# PowerSupply.net
KiCad netlist of a schematic drawn in Altium Designer
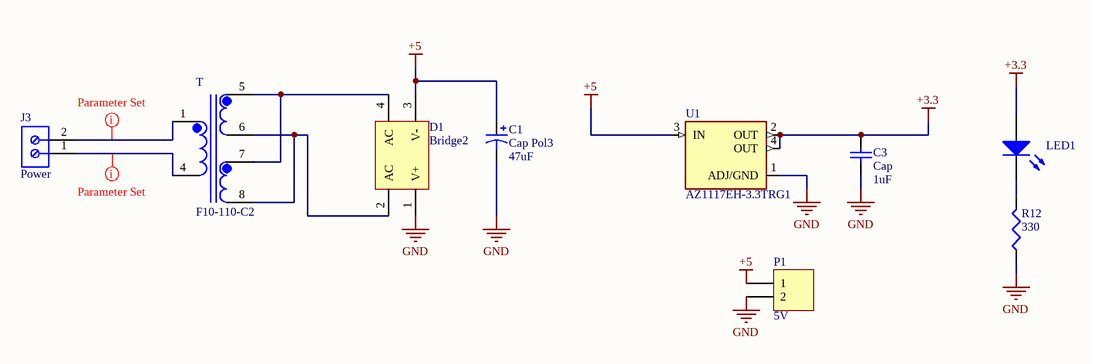
[diagram p0: PowerSupply.SchDoc]

(export (version "E")
  (design (tool "Eeschema 10.0.6"))
  (components
    (comp (ref "C1")
      (value "Cap Pol3")
      (footprint "2.5mmCap")
      (description "Polarized Capacitor (Surface Mount)")
      (fields (field (name "ALTIUM_VALUE") "47uF") (field (name "PUBLISHER") "Altium Limited"))
      (libsource (lib "STM32F4_Breakout") (part "Cap Pol3"))
    )
    (comp (ref "C3")
      (value "Cap")
      (footprint "1608[0603]")
      (description "Capacitor")
      (fields (field (name "ALTIUM_VALUE") "1uF") (field (name "PUBLISHER") "Altium Limited"))
      (libsource (lib "Miscellaneous Devices") (part "Cap"))
    )
    (comp (ref "D1")
      (value "Bridge2")
      (footprint "SOP250P700X300-4N")
      (description "Diode Bridge")
      (fields (field (name "PUBLISHER") "Altium Limited"))
      (libsource (lib "Miscellaneous Devices") (part "Bridge2"))
    )
    (comp (ref "J3")
      (value "Power")
      (footprint "691137710002")
      (description "Series 1377 - 5.00 mm Horizontal Entry with Pressure Clamp WR-TBL, 2 pin")
      (fields
        (field (name "MANUFACTURER") "Wurth Elektronik")
        (field (name "PART NUMBER") "691137710002")
        (field (name "PUBLISHER") "WurthElektronik")
      )
      (libsource (lib "Altium Content Vault") (part "WE-CN-1P-F-TB2"))
    )
    (comp (ref "LED1")
      (value "150120BS75000")
      (footprint "1206_A")
      (description "SMD mono-color Chip LED, WL-SMCW, Blue")
      (fields (field (name "MANUFACTURER") "Wuerth Elektronik"))
      (libsource (lib "Altium Content Vault") (part "WE-LED_K1A2-2"))
    )
    (comp (ref "P1")
      (value "5V")
      (footprint "HDR1X2H")
      (description "Header, 2-Pin, Right Angle")
      (fields (field (name "PUBLISHER") "Altium Limited"))
      (libsource (lib "Miscellaneous Connectors") (part "Header 2H"))
    )
    (comp (ref "R12")
      (value "330")
      (footprint "1608[0603]")
      (description "Resistor")
      (fields
        (field (name "LCSC PART #") "C25804")
        (field (name "Comment") "Res3")
        (field (name "PUBLISHER") "Altium Limited")
      )
      (libsource (lib "STM32F4_Breakout") (part "Res3_2"))
    )
    (comp (ref "T")
      (value "F10-110-C2")
      (footprint "XFMR_F10-110")
      (description "F10 Series Single Primary Dual Secondary Split Bobbin Class 2 Transformer")
      (fields (field (name "DIGI-KEY_PART_NUMBER") "237-1557-ND") (field (name "MF") "Triad Magnetics"))
      (libsource (lib "F10-110-C2") (part "F10-110-C2"))
    )
    (comp (ref "U1")
      (value "AZ1117EH-3.3TRG1")
      (footprint "SOT230P700X180-4N")
      (description "Linear Voltage Regulator IC 1 Output 1A SOT-223")
      (fields (field (name "MF") "Diodes Inc."))
      (libsource (lib "AZ1117EH-3.3TRG1") (part "AZ1117EH-3.3TRG1"))
    )
  )
  (nets
    (net (code "1") (name "+3.3") (class "Default")
      (node (ref "C3") (pin "2") (pinfunction "2_2") (pintype "passive"))
      (node (ref "LED1") (pin "2") (pinfunction "A_2") (pintype "passive"))
      (node (ref "U1") (pin "2") (pinfunction "OUT_2") (pintype "output"))
      (node (ref "U1") (pin "4") (pinfunction "OUT_4") (pintype "output"))
    )
    (net (code "2") (name "+5") (class "Default")
      (node (ref "C1") (pin "1") (pinfunction "1_1") (pintype "passive"))
      (node (ref "D1") (pin "3") (pinfunction "V-_3") (pintype "passive"))
      (node (ref "P1") (pin "1") (pinfunction "1_1") (pintype "passive"))
      (node (ref "U1") (pin "3") (pinfunction "IN_3") (pintype "input"))
    )
    (net (code "3") (name "GND") (class "Default")
      (node (ref "C1") (pin "2") (pinfunction "2_2") (pintype "passive"))
      (node (ref "C3") (pin "1") (pinfunction "1_1") (pintype "passive"))
      (node (ref "D1") (pin "1") (pinfunction "V+_1") (pintype "passive"))
      (node (ref "P1") (pin "2") (pinfunction "2_2") (pintype "passive"))
      (node (ref "R12") (pin "1") (pinfunction "1_1") (pintype "passive"))
      (node (ref "U1") (pin "1") (pinfunction "ADJ/GND_1") (pintype "power_in"))
    )
    (net (code "4") (name "Net-(D1-AC-Pad2)") (class "Default")
      (node (ref "D1") (pin "2") (pinfunction "AC_2") (pintype "passive"))
      (node (ref "T") (pin "6") (pinfunction "6_6") (pintype "passive"))
      (node (ref "T") (pin "8") (pinfunction "8_8") (pintype "passive"))
    )
    (net (code "5") (name "Net-(D1-AC-Pad4)") (class "Default")
      (node (ref "D1") (pin "4") (pinfunction "AC_4") (pintype "passive"))
      (node (ref "T") (pin "5") (pinfunction "5_5") (pintype "passive"))
      (node (ref "T") (pin "7") (pinfunction "7_7") (pintype "passive"))
    )
    (net (code "6") (name "Net-(J3-Pad1)") (class "Default")
      (node (ref "J3") (pin "1") (pinfunction "1_1") (pintype "passive"))
      (node (ref "T") (pin "4") (pinfunction "4_4") (pintype "passive"))
    )
    (net (code "7") (name "Net-(J3-Pad2)") (class "Default")
      (node (ref "J3") (pin "2") (pinfunction "2_2") (pintype "passive"))
      (node (ref "T") (pin "1") (pinfunction "1_1") (pintype "passive"))
    )
    (net (code "8") (name "Net-(LED1-K)") (class "Default")
      (node (ref "LED1") (pin "1") (pinfunction "K_1") (pintype "passive"))
      (node (ref "R12") (pin "2") (pinfunction "2_2") (pintype "passive"))
    )
  )
)
